# esp.net
KiCad netlist of a schematic drawn in EAGLE
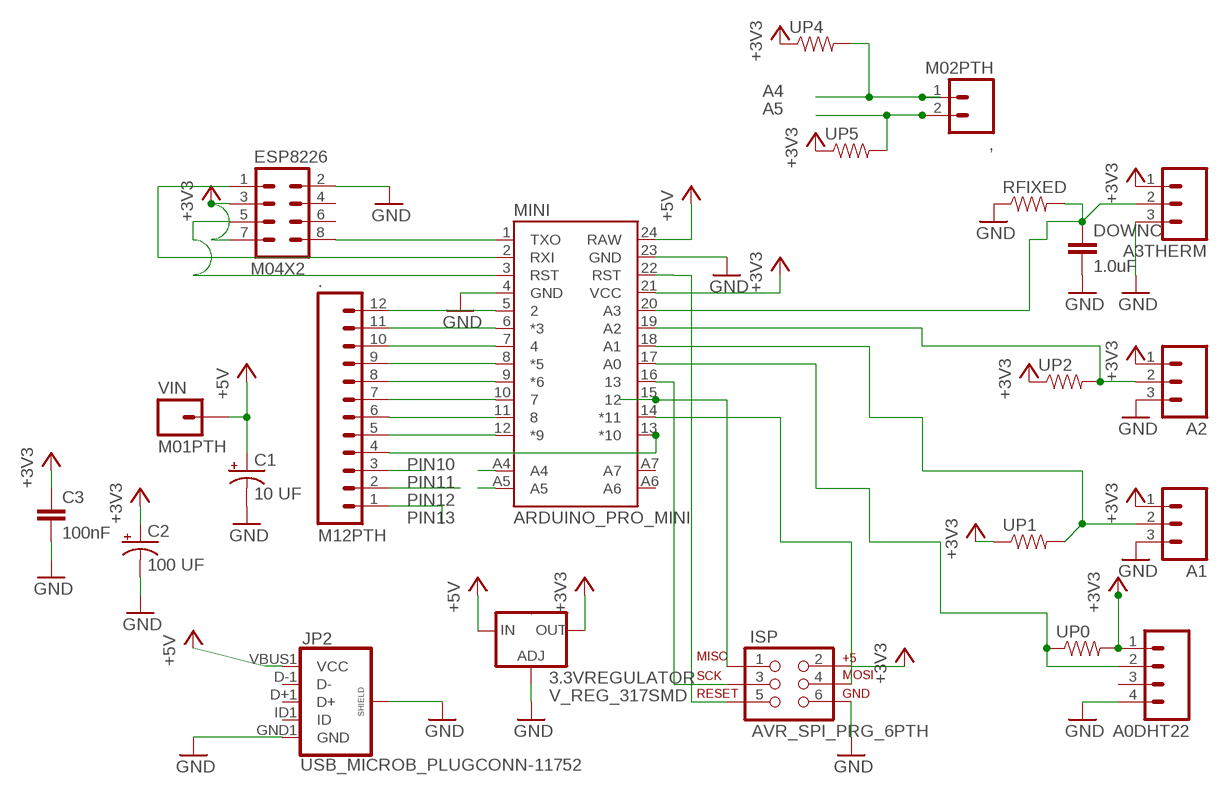
[diagram p0: schematic, sheet 1]

(export (version "E")
  (design (tool "Eeschema 10.0.6"))
  (components
    (comp (ref ",")
      (value "M02PTH")
      (footprint "eagle-import:1X02")
      (libsource (lib "eagle-import") (part "M02PTH"))
    )
    (comp (ref ".")
      (value "M12PTH")
      (footprint "eagle-import:1X12")
      (libsource (lib "eagle-import") (part "M12PTH"))
    )
    (comp (ref "3.3VREGULATOR")
      (value "V_REG_317SMD")
      (footprint "eagle-import:SOT223")
      (libsource (lib "eagle-import") (part "V_REG_317SMD"))
    )
    (comp (ref "A0DHT22")
      (value "M04PTH")
      (footprint "eagle-import:1X04")
      (libsource (lib "eagle-import") (part "M04PTH"))
    )
    (comp (ref "A1")
      (value "M03PTH")
      (footprint "eagle-import:1X03")
      (libsource (lib "eagle-import") (part "M03PTH"))
    )
    (comp (ref "A2")
      (value "M03PTH")
      (footprint "eagle-import:1X03")
      (libsource (lib "eagle-import") (part "M03PTH"))
    )
    (comp (ref "A3THERM")
      (value "M03PTH")
      (footprint "eagle-import:1X03")
      (libsource (lib "eagle-import") (part "M03PTH"))
    )
    (comp (ref "C1")
      (value "10 UF")
      (footprint "eagle-import:CPOL-RADIAL-10UF-25V")
      (libsource (lib "eagle-import") (part "10UF-25V-20%(PTH)"))
    )
    (comp (ref "C2")
      (value "100 UF")
      (footprint "eagle-import:CPOL-RADIAL-10UF-25V")
      (libsource (lib "eagle-import") (part "10UF-25V-20%(PTH)"))
    )
    (comp (ref "C3")
      (value "100nF")
      (footprint "eagle-import:0805")
      (libsource (lib "eagle-import") (part "1.0UF-25V-+80/-20(0805)"))
    )
    (comp (ref "DOWNC")
      (value "1.0uF")
      (footprint "eagle-import:0805")
      (libsource (lib "eagle-import") (part "1.0UF-25V-+80/-20(0805)"))
    )
    (comp (ref "ESP8226")
      (value "M04X2")
      (footprint "eagle-import:2X4")
      (libsource (lib "eagle-import") (part "M04X2"))
    )
    (comp (ref "ISP")
      (value "AVR_SPI_PRG_6PTH")
      (footprint "eagle-import:2X3")
      (libsource (lib "eagle-import") (part "AVR_SPI_PRG_6PTH"))
    )
    (comp (ref "JP2")
      (value "USB_MICROB_PLUGCONN-11752")
      (footprint "eagle-import:USB-B-MICRO-SMD_V03")
      (libsource (lib "eagle-import") (part "USB_MICROB_PLUGCONN-11752"))
    )
    (comp (ref "MINI")
      (value "ARDUINO_PRO_MINI")
      (footprint "eagle-import:ARDUINO_PRO_MINI")
      (libsource (lib "eagle-import") (part "ARDUINO_PRO_MINI"))
    )
    (comp (ref "RFIXED")
      (value "0.3OHM-1/8W-1%(0805)")
      (footprint "eagle-import:0805")
      (libsource (lib "eagle-import") (part "0.3OHM-1/8W-1%(0805)"))
    )
    (comp (ref "UP0")
      (value "0.3OHM-1/8W-1%(0805)")
      (footprint "eagle-import:0805")
      (libsource (lib "eagle-import") (part "0.3OHM-1/8W-1%(0805)"))
    )
    (comp (ref "UP1")
      (value "0.3OHM-1/8W-1%(0805)")
      (footprint "eagle-import:0805")
      (libsource (lib "eagle-import") (part "0.3OHM-1/8W-1%(0805)"))
    )
    (comp (ref "UP2")
      (value "0.3OHM-1/8W-1%(0805)")
      (footprint "eagle-import:0805")
      (libsource (lib "eagle-import") (part "0.3OHM-1/8W-1%(0805)"))
    )
    (comp (ref "UP4")
      (value "0.3OHM-1/8W-1%(0805)")
      (footprint "eagle-import:0805")
      (libsource (lib "eagle-import") (part "0.3OHM-1/8W-1%(0805)"))
    )
    (comp (ref "UP5")
      (value "0.3OHM-1/8W-1%(0805)")
      (footprint "eagle-import:0805")
      (libsource (lib "eagle-import") (part "0.3OHM-1/8W-1%(0805)"))
    )
    (comp (ref "VIN")
      (value "M01PTH")
      (footprint "eagle-import:1X01")
      (libsource (lib "eagle-import") (part "M01PTH"))
    )
  )
  (nets
    (net (code "1") (name "+3V3") (class "Default")
      (node (ref "3.3VREGULATOR") (pin "2") (pinfunction "OUT_2") (pintype "output"))
      (node (ref "A0DHT22") (pin "1") (pinfunction "1_1") (pintype "passive"))
      (node (ref "A1") (pin "1") (pinfunction "1_1") (pintype "passive"))
      (node (ref "A2") (pin "1") (pinfunction "1_1") (pintype "passive"))
      (node (ref "A3THERM") (pin "1") (pinfunction "1_1") (pintype "passive"))
      (node (ref "C2") (pin "1") (pinfunction "+_1") (pintype "passive"))
      (node (ref "C3") (pin "1") (pinfunction "1_1") (pintype "passive"))
      (node (ref "ESP8226") (pin "3") (pinfunction "3_3") (pintype "passive"))
      (node (ref "ESP8226") (pin "7") (pinfunction "7_7") (pintype "passive"))
      (node (ref "ISP") (pin "2") (pinfunction "2_2") (pintype "passive"))
      (node (ref "MINI") (pin "21") (pinfunction "VCC_21") (pintype "bidirectional"))
      (node (ref "UP0") (pin "2") (pinfunction "2_2") (pintype "passive"))
      (node (ref "UP1") (pin "1") (pinfunction "1_1") (pintype "passive"))
      (node (ref "UP2") (pin "1") (pinfunction "1_1") (pintype "passive"))
      (node (ref "UP4") (pin "1") (pinfunction "1_1") (pintype "passive"))
      (node (ref "UP5") (pin "1") (pinfunction "1_1") (pintype "passive"))
    )
    (net (code "2") (name "+5V") (class "Default")
      (node (ref "3.3VREGULATOR") (pin "3") (pinfunction "IN_3") (pintype "input"))
      (node (ref "C1") (pin "1") (pinfunction "+_1") (pintype "passive"))
      (node (ref "JP2") (pin "VBUS1") (pinfunction "VCC_VBUS1") (pintype "bidirectional"))
      (node (ref "MINI") (pin "24") (pinfunction "RAW_24") (pintype "bidirectional"))
      (node (ref "VIN") (pin "1") (pinfunction "1_1") (pintype "passive"))
    )
    (net (code "3") (name "/A4") (class "Default")
      (node (ref ",") (pin "1") (pinfunction "1_1") (pintype "passive"))
      (node (ref "MINI") (pin "A4") (pinfunction "A4_A4") (pintype "bidirectional"))
      (node (ref "UP4") (pin "2") (pinfunction "2_2") (pintype "passive"))
    )
    (net (code "4") (name "/A5") (class "Default")
      (node (ref ",") (pin "2") (pinfunction "2_2") (pintype "passive"))
      (node (ref "MINI") (pin "A5") (pinfunction "A5_A5") (pintype "bidirectional"))
      (node (ref "UP5") (pin "2") (pinfunction "2_2") (pintype "passive"))
    )
    (net (code "5") (name "/PIN10") (class "Default")
      (node (ref ".") (pin "4") (pinfunction "4_4") (pintype "passive"))
      (node (ref "MINI") (pin "13") (pinfunction "*10_13") (pintype "bidirectional"))
    )
    (net (code "6") (name "/PIN11") (class "Default")
      (node (ref ".") (pin "3") (pinfunction "3_3") (pintype "passive"))
      (node (ref "ISP") (pin "4") (pinfunction "4_4") (pintype "passive"))
      (node (ref "MINI") (pin "14") (pinfunction "*11_14") (pintype "bidirectional"))
    )
    (net (code "7") (name "/PIN12") (class "Default")
      (node (ref ".") (pin "2") (pinfunction "2_2") (pintype "passive"))
      (node (ref "ISP") (pin "1") (pinfunction "1_1") (pintype "passive"))
      (node (ref "MINI") (pin "15") (pinfunction "12_15") (pintype "bidirectional"))
    )
    (net (code "8") (name "/PIN13") (class "Default")
      (node (ref ".") (pin "1") (pinfunction "1_1") (pintype "passive"))
      (node (ref "ISP") (pin "3") (pinfunction "3_3") (pintype "passive"))
      (node (ref "MINI") (pin "16") (pinfunction "13_16") (pintype "bidirectional"))
    )
    (net (code "9") (name "GND") (class "Default")
      (node (ref "3.3VREGULATOR") (pin "1") (pinfunction "ADJ_1") (pintype "input"))
      (node (ref "A0DHT22") (pin "4") (pinfunction "4_4") (pintype "passive"))
      (node (ref "A1") (pin "3") (pinfunction "3_3") (pintype "passive"))
      (node (ref "A2") (pin "3") (pinfunction "3_3") (pintype "passive"))
      (node (ref "A3THERM") (pin "3") (pinfunction "3_3") (pintype "passive"))
      (node (ref "C1") (pin "2") (pinfunction "-_2") (pintype "passive"))
      (node (ref "C2") (pin "2") (pinfunction "-_2") (pintype "passive"))
      (node (ref "C3") (pin "2") (pinfunction "2_2") (pintype "passive"))
      (node (ref "DOWNC") (pin "2") (pinfunction "2_2") (pintype "passive"))
      (node (ref "ESP8226") (pin "2") (pinfunction "2_2") (pintype "passive"))
      (node (ref "ISP") (pin "6") (pinfunction "6_6") (pintype "passive"))
      (node (ref "JP2") (pin "GND1") (pinfunction "GND_GND1") (pintype "bidirectional"))
      (node (ref "JP2") (pin "SHIELD1") (pinfunction "SHIELD_SHIELD1") (pintype "bidirectional"))
      (node (ref "JP2") (pin "SHIELD2") (pinfunction "SHIELD_SHIELD2") (pintype "bidirectional"))
      (node (ref "JP2") (pin "SHIELD3") (pinfunction "SHIELD_SHIELD3") (pintype "bidirectional"))
      (node (ref "MINI") (pin "23") (pinfunction "GND_23") (pintype "bidirectional"))
      (node (ref "MINI") (pin "4") (pinfunction "GND_4") (pintype "bidirectional"))
      (node (ref "RFIXED") (pin "1") (pinfunction "1_1") (pintype "passive"))
    )
    (net (code "10") (name "Net-(ESP8226-Pad5)") (class "Default")
      (node (ref "ESP8226") (pin "5") (pinfunction "5_5") (pintype "passive"))
      (node (ref "MINI") (pin "3") (pinfunction "RST_3") (pintype "bidirectional"))
    )
    (net (code "11") (name "Net-(ISP-Pad5)") (class "Default")
      (node (ref "ISP") (pin "5") (pinfunction "5_5") (pintype "passive"))
      (node (ref "MINI") (pin "22") (pinfunction "RST_22") (pintype "bidirectional"))
    )
    (net (code "12") (name "Net-(MINI-*3)") (class "Default")
      (node (ref ".") (pin "11") (pinfunction "11_11") (pintype "passive"))
      (node (ref "MINI") (pin "6") (pinfunction "*3_6") (pintype "bidirectional"))
    )
    (net (code "13") (name "Net-(MINI-*5)") (class "Default")
      (node (ref ".") (pin "9") (pinfunction "9_9") (pintype "passive"))
      (node (ref "MINI") (pin "8") (pinfunction "*5_8") (pintype "bidirectional"))
    )
    (net (code "14") (name "Net-(MINI-*6)") (class "Default")
      (node (ref ".") (pin "8") (pinfunction "8_8") (pintype "passive"))
      (node (ref "MINI") (pin "9") (pinfunction "*6_9") (pintype "bidirectional"))
    )
    (net (code "15") (name "Net-(MINI-*9)") (class "Default")
      (node (ref ".") (pin "5") (pinfunction "5_5") (pintype "passive"))
      (node (ref "MINI") (pin "12") (pinfunction "*9_12") (pintype "bidirectional"))
    )
    (net (code "16") (name "Net-(MINI-2)") (class "Default")
      (node (ref ".") (pin "12") (pinfunction "12_12") (pintype "passive"))
      (node (ref "MINI") (pin "5") (pinfunction "2_5") (pintype "bidirectional"))
    )
    (net (code "17") (name "Net-(MINI-4)") (class "Default")
      (node (ref ".") (pin "10") (pinfunction "10_10") (pintype "passive"))
      (node (ref "MINI") (pin "7") (pinfunction "4_7") (pintype "bidirectional"))
    )
    (net (code "18") (name "Net-(MINI-7)") (class "Default")
      (node (ref ".") (pin "7") (pinfunction "7_7") (pintype "passive"))
      (node (ref "MINI") (pin "10") (pinfunction "7_10") (pintype "bidirectional"))
    )
    (net (code "19") (name "Net-(MINI-8)") (class "Default")
      (node (ref ".") (pin "6") (pinfunction "6_6") (pintype "passive"))
      (node (ref "MINI") (pin "11") (pinfunction "8_11") (pintype "bidirectional"))
    )
    (net (code "20") (name "Net-(MINI-A0)") (class "Default")
      (node (ref "A0DHT22") (pin "2") (pinfunction "2_2") (pintype "passive"))
      (node (ref "MINI") (pin "17") (pinfunction "A0_17") (pintype "bidirectional"))
      (node (ref "UP0") (pin "1") (pinfunction "1_1") (pintype "passive"))
    )
    (net (code "21") (name "Net-(MINI-A1)") (class "Default")
      (node (ref "A1") (pin "2") (pinfunction "2_2") (pintype "passive"))
      (node (ref "MINI") (pin "18") (pinfunction "A1_18") (pintype "bidirectional"))
      (node (ref "UP1") (pin "2") (pinfunction "2_2") (pintype "passive"))
    )
    (net (code "22") (name "Net-(MINI-A2)") (class "Default")
      (node (ref "A2") (pin "2") (pinfunction "2_2") (pintype "passive"))
      (node (ref "MINI") (pin "19") (pinfunction "A2_19") (pintype "bidirectional"))
      (node (ref "UP2") (pin "2") (pinfunction "2_2") (pintype "passive"))
    )
    (net (code "23") (name "Net-(MINI-A3)") (class "Default")
      (node (ref "A3THERM") (pin "2") (pinfunction "2_2") (pintype "passive"))
      (node (ref "DOWNC") (pin "1") (pinfunction "1_1") (pintype "passive"))
      (node (ref "MINI") (pin "20") (pinfunction "A3_20") (pintype "bidirectional"))
      (node (ref "RFIXED") (pin "2") (pinfunction "2_2") (pintype "passive"))
    )
    (net (code "24") (name "Net-(MINI-RXI)") (class "Default")
      (node (ref "ESP8226") (pin "1") (pinfunction "1_1") (pintype "passive"))
      (node (ref "MINI") (pin "2") (pinfunction "RXI_2") (pintype "bidirectional"))
    )
    (net (code "25") (name "Net-(MINI-TXO)") (class "Default")
      (node (ref "ESP8226") (pin "8") (pinfunction "8_8") (pintype "passive"))
      (node (ref "MINI") (pin "1") (pinfunction "TXO_1") (pintype "bidirectional"))
    )
    (net (code "26") (name "unconnected-(A0DHT22-Pad3)") (class "Default")
      (node (ref "A0DHT22") (pin "3") (pinfunction "3_3") (pintype "passive"))
    )
    (net (code "27") (name "unconnected-(ESP8226-Pad4)") (class "Default")
      (node (ref "ESP8226") (pin "4") (pinfunction "4_4") (pintype "passive"))
    )
    (net (code "28") (name "unconnected-(ESP8226-Pad6)") (class "Default")
      (node (ref "ESP8226") (pin "6") (pinfunction "6_6") (pintype "passive"))
    )
    (net (code "29") (name "unconnected-(JP2-D+-PadD+1)") (class "Default")
      (node (ref "JP2") (pin "D+1") (pinfunction "D+_D+1") (pintype "bidirectional"))
    )
    (net (code "30") (name "unconnected-(JP2-D--PadD-1)") (class "Default")
      (node (ref "JP2") (pin "D-1") (pinfunction "D-_D-1") (pintype "bidirectional"))
    )
    (net (code "31") (name "unconnected-(JP2-ID-PadID1)") (class "Default")
      (node (ref "JP2") (pin "ID1") (pinfunction "ID_ID1") (pintype "bidirectional"))
    )
    (net (code "32") (name "unconnected-(MINI-PadA6)") (class "Default")
      (node (ref "MINI") (pin "A6") (pinfunction "A6_A6") (pintype "bidirectional"))
    )
    (net (code "33") (name "unconnected-(MINI-PadA7)") (class "Default")
      (node (ref "MINI") (pin "A7") (pinfunction "A7_A7") (pintype "bidirectional"))
    )
  )
)
